# FlexWatch.net
KiCad netlist of a schematic drawn in EAGLE
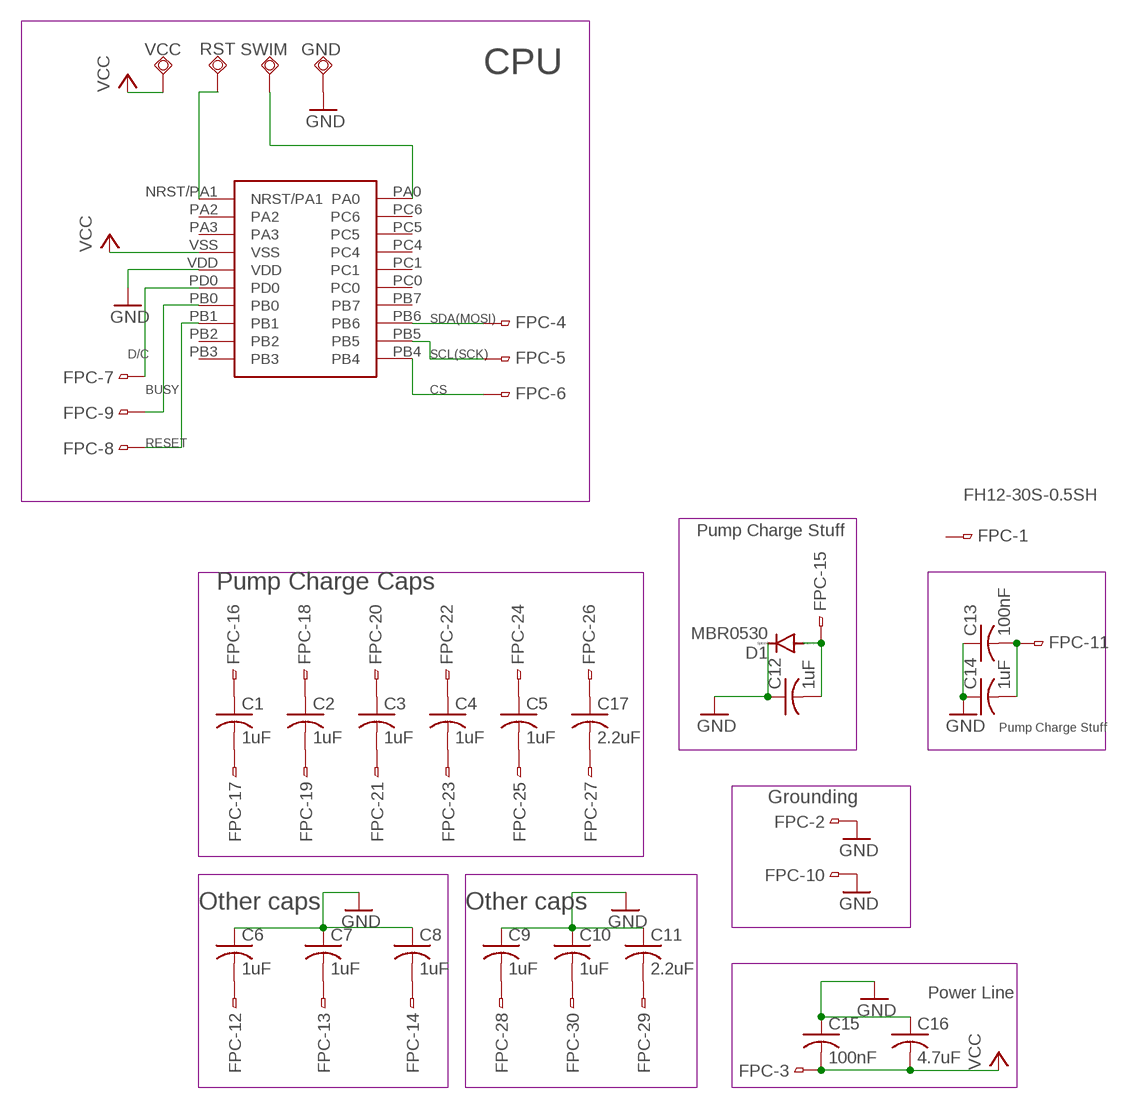
[diagram p0: schematic, sheet 1]

(export (version "E")
  (design (tool "Eeschema 10.0.6"))
  (components
    (comp (ref "C1")
      (value "1uF")
      (footprint "eagle-import:C0805")
      (libsource (lib "eagle-import") (part "C-USC0805"))
    )
    (comp (ref "C2")
      (value "1uF")
      (footprint "eagle-import:C0805")
      (libsource (lib "eagle-import") (part "C-USC0805"))
    )
    (comp (ref "C3")
      (value "1uF")
      (footprint "eagle-import:C0805")
      (libsource (lib "eagle-import") (part "C-USC0805"))
    )
    (comp (ref "C4")
      (value "1uF")
      (footprint "eagle-import:C0805")
      (libsource (lib "eagle-import") (part "C-USC0805"))
    )
    (comp (ref "C5")
      (value "1uF")
      (footprint "eagle-import:C0805")
      (libsource (lib "eagle-import") (part "C-USC0805"))
    )
    (comp (ref "C6")
      (value "1uF")
      (footprint "eagle-import:C0805")
      (libsource (lib "eagle-import") (part "C-USC0805"))
    )
    (comp (ref "C7")
      (value "1uF")
      (footprint "eagle-import:C0805")
      (libsource (lib "eagle-import") (part "C-USC0805"))
    )
    (comp (ref "C8")
      (value "1uF")
      (footprint "eagle-import:C0805")
      (libsource (lib "eagle-import") (part "C-USC0805"))
    )
    (comp (ref "C9")
      (value "1uF")
      (footprint "eagle-import:C0805")
      (libsource (lib "eagle-import") (part "C-USC0805"))
    )
    (comp (ref "C10")
      (value "1uF")
      (footprint "eagle-import:C0805")
      (libsource (lib "eagle-import") (part "C-USC0805"))
    )
    (comp (ref "C11")
      (value "2.2uF")
      (footprint "eagle-import:C1206")
      (libsource (lib "eagle-import") (part "C-USC1206"))
    )
    (comp (ref "C12")
      (value "1uF")
      (footprint "eagle-import:C0805")
      (libsource (lib "eagle-import") (part "C-USC0805"))
    )
    (comp (ref "C13")
      (value "100nF")
      (footprint "eagle-import:C0805")
      (libsource (lib "eagle-import") (part "C-USC0805"))
    )
    (comp (ref "C14")
      (value "1uF")
      (footprint "eagle-import:C0805")
      (libsource (lib "eagle-import") (part "C-USC0805"))
    )
    (comp (ref "C15")
      (value "100nF")
      (footprint "eagle-import:C0805")
      (libsource (lib "eagle-import") (part "C-USC0805"))
    )
    (comp (ref "C16")
      (value "4.7uF")
      (footprint "eagle-import:C0805")
      (libsource (lib "eagle-import") (part "C-USC0805"))
    )
    (comp (ref "C17")
      (value "2.2uF")
      (footprint "eagle-import:C1206")
      (libsource (lib "eagle-import") (part "C-USC1206"))
    )
    (comp (ref "D1")
      (value "MBR0530")
      (footprint "eagle-import:SOD-123_MINI-SMA")
      (libsource (lib "eagle-import") (part "CGRM400-G1"))
    )
    (comp (ref "FPC")
      (value "FH12-30S-0.5SH")
      (footprint "eagle-import:FH12-30S-0.5SH")
      (fields (field (name "MPN") "FH12-30S-0.5SH(55)"))
      (libsource (lib "eagle-import") (part "FH12-30S-0.5SH"))
    )
    (comp (ref "GND")
      (value "TPSQTP18SQ")
      (footprint "eagle-import:TP18SQ")
      (libsource (lib "eagle-import") (part "TPSQTP18SQ"))
    )
    (comp (ref "RST")
      (value "TPSQTP18SQ")
      (footprint "eagle-import:TP18SQ")
      (libsource (lib "eagle-import") (part "TPSQTP18SQ"))
    )
    (comp (ref "SWIM")
      (value "TPSQTP18SQ")
      (footprint "eagle-import:TP18SQ")
      (libsource (lib "eagle-import") (part "TPSQTP18SQ"))
    )
    (comp (ref "U$1")
      (value "STM8L151F3")
      (footprint "eagle-import:UFQFPN-20")
      (libsource (lib "eagle-import") (part "STM8L151F3"))
    )
    (comp (ref "VCC")
      (value "TPSQTP18SQ")
      (footprint "eagle-import:TP18SQ")
      (libsource (lib "eagle-import") (part "TPSQTP18SQ"))
    )
  )
  (nets
    (net (code "1") (name "/BUSY") (class "Default")
      (node (ref "FPC") (pin "9") (pinfunction "1_9") (pintype "passive"))
      (node (ref "U$1") (pin "PB0") (pinfunction "PB0_PB0") (pintype "bidirectional"))
    )
    (net (code "2") (name "/CS") (class "Default")
      (node (ref "FPC") (pin "6") (pinfunction "1_6") (pintype "passive"))
      (node (ref "U$1") (pin "PB4") (pinfunction "PB4_PB4") (pintype "bidirectional"))
    )
    (net (code "3") (name "/D{slash}C") (class "Default")
      (node (ref "FPC") (pin "7") (pinfunction "1_7") (pintype "passive"))
      (node (ref "U$1") (pin "PD0") (pinfunction "PD0_PD0") (pintype "bidirectional"))
    )
    (net (code "4") (name "/RESET") (class "Default")
      (node (ref "FPC") (pin "8") (pinfunction "1_8") (pintype "passive"))
      (node (ref "U$1") (pin "PB1") (pinfunction "PB1_PB1") (pintype "bidirectional"))
    )
    (net (code "5") (name "/SCL(SCK)") (class "Default")
      (node (ref "FPC") (pin "5") (pinfunction "1_5") (pintype "passive"))
      (node (ref "U$1") (pin "PB5") (pinfunction "PB5_PB5") (pintype "bidirectional"))
    )
    (net (code "6") (name "/SDA(MOSI)") (class "Default")
      (node (ref "FPC") (pin "4") (pinfunction "1_4") (pintype "passive"))
      (node (ref "U$1") (pin "PB6") (pinfunction "PB6_PB6") (pintype "bidirectional"))
    )
    (net (code "7") (name "GND") (class "Default")
      (node (ref "C10") (pin "1") (pinfunction "1_1") (pintype "passive"))
      (node (ref "C11") (pin "1") (pinfunction "1_1") (pintype "passive"))
      (node (ref "C12") (pin "1") (pinfunction "1_1") (pintype "passive"))
      (node (ref "C13") (pin "1") (pinfunction "1_1") (pintype "passive"))
      (node (ref "C14") (pin "1") (pinfunction "1_1") (pintype "passive"))
      (node (ref "C15") (pin "1") (pinfunction "1_1") (pintype "passive"))
      (node (ref "C16") (pin "1") (pinfunction "1_1") (pintype "passive"))
      (node (ref "C6") (pin "1") (pinfunction "1_1") (pintype "passive"))
      (node (ref "C7") (pin "1") (pinfunction "1_1") (pintype "passive"))
      (node (ref "C8") (pin "1") (pinfunction "1_1") (pintype "passive"))
      (node (ref "C9") (pin "1") (pinfunction "1_1") (pintype "passive"))
      (node (ref "D1") (pin "C") (pinfunction "C_C") (pintype "passive"))
      (node (ref "FPC") (pin "10") (pinfunction "1_10") (pintype "passive"))
      (node (ref "FPC") (pin "2") (pinfunction "1_2") (pintype "passive"))
      (node (ref "GND") (pin "TP") (pinfunction "TP_TP") (pintype "input"))
      (node (ref "U$1") (pin "VDD") (pinfunction "VDD_VDD") (pintype "bidirectional"))
    )
    (net (code "8") (name "Net-(FPCC-1)") (class "Default")
      (node (ref "C13") (pin "2") (pinfunction "2_2") (pintype "passive"))
      (node (ref "C14") (pin "2") (pinfunction "2_2") (pintype "passive"))
      (node (ref "FPC") (pin "11") (pinfunction "1_11") (pintype "passive"))
    )
    (net (code "9") (name "Net-(FPCD-1)") (class "Default")
      (node (ref "C6") (pin "2") (pinfunction "2_2") (pintype "passive"))
      (node (ref "FPC") (pin "12") (pinfunction "1_12") (pintype "passive"))
    )
    (net (code "10") (name "Net-(FPCE-1)") (class "Default")
      (node (ref "C7") (pin "2") (pinfunction "2_2") (pintype "passive"))
      (node (ref "FPC") (pin "13") (pinfunction "1_13") (pintype "passive"))
    )
    (net (code "11") (name "Net-(FPCF-1)") (class "Default")
      (node (ref "C8") (pin "2") (pinfunction "2_2") (pintype "passive"))
      (node (ref "FPC") (pin "14") (pinfunction "1_14") (pintype "passive"))
    )
    (net (code "12") (name "Net-(FPCG-1)") (class "Default")
      (node (ref "C12") (pin "2") (pinfunction "2_2") (pintype "passive"))
      (node (ref "D1") (pin "A") (pinfunction "A_A") (pintype "passive"))
      (node (ref "FPC") (pin "15") (pinfunction "1_15") (pintype "passive"))
    )
    (net (code "13") (name "Net-(FPCH-1)") (class "Default")
      (node (ref "C1") (pin "1") (pinfunction "1_1") (pintype "passive"))
      (node (ref "FPC") (pin "16") (pinfunction "1_16") (pintype "passive"))
    )
    (net (code "14") (name "Net-(FPCI-1)") (class "Default")
      (node (ref "C1") (pin "2") (pinfunction "2_2") (pintype "passive"))
      (node (ref "FPC") (pin "17") (pinfunction "1_17") (pintype "passive"))
    )
    (net (code "15") (name "Net-(FPCJ-1)") (class "Default")
      (node (ref "C2") (pin "1") (pinfunction "1_1") (pintype "passive"))
      (node (ref "FPC") (pin "18") (pinfunction "1_18") (pintype "passive"))
    )
    (net (code "16") (name "Net-(FPCK-1)") (class "Default")
      (node (ref "C2") (pin "2") (pinfunction "2_2") (pintype "passive"))
      (node (ref "FPC") (pin "19") (pinfunction "1_19") (pintype "passive"))
    )
    (net (code "17") (name "Net-(FPCM-1)") (class "Default")
      (node (ref "C3") (pin "1") (pinfunction "1_1") (pintype "passive"))
      (node (ref "FPC") (pin "20") (pinfunction "1_20") (pintype "passive"))
    )
    (net (code "18") (name "Net-(FPCN-1)") (class "Default")
      (node (ref "C3") (pin "2") (pinfunction "2_2") (pintype "passive"))
      (node (ref "FPC") (pin "21") (pinfunction "1_21") (pintype "passive"))
    )
    (net (code "19") (name "Net-(FPCO-1)") (class "Default")
      (node (ref "C4") (pin "1") (pinfunction "1_1") (pintype "passive"))
      (node (ref "FPC") (pin "22") (pinfunction "1_22") (pintype "passive"))
    )
    (net (code "20") (name "Net-(FPCP-1)") (class "Default")
      (node (ref "C4") (pin "2") (pinfunction "2_2") (pintype "passive"))
      (node (ref "FPC") (pin "23") (pinfunction "1_23") (pintype "passive"))
    )
    (net (code "21") (name "Net-(FPCQ-1)") (class "Default")
      (node (ref "C5") (pin "1") (pinfunction "1_1") (pintype "passive"))
      (node (ref "FPC") (pin "24") (pinfunction "1_24") (pintype "passive"))
    )
    (net (code "22") (name "Net-(FPCR-1)") (class "Default")
      (node (ref "C5") (pin "2") (pinfunction "2_2") (pintype "passive"))
      (node (ref "FPC") (pin "25") (pinfunction "1_25") (pintype "passive"))
    )
    (net (code "23") (name "Net-(FPCS-1)") (class "Default")
      (node (ref "C17") (pin "1") (pinfunction "1_1") (pintype "passive"))
      (node (ref "FPC") (pin "26") (pinfunction "1_26") (pintype "passive"))
    )
    (net (code "24") (name "Net-(FPCT-1)") (class "Default")
      (node (ref "C17") (pin "2") (pinfunction "2_2") (pintype "passive"))
      (node (ref "FPC") (pin "27") (pinfunction "1_27") (pintype "passive"))
    )
    (net (code "25") (name "Net-(FPCU-1)") (class "Default")
      (node (ref "C9") (pin "2") (pinfunction "2_2") (pintype "passive"))
      (node (ref "FPC") (pin "28") (pinfunction "1_28") (pintype "passive"))
    )
    (net (code "26") (name "Net-(FPCV-1)") (class "Default")
      (node (ref "C11") (pin "2") (pinfunction "2_2") (pintype "passive"))
      (node (ref "FPC") (pin "29") (pinfunction "1_29") (pintype "passive"))
    )
    (net (code "27") (name "Net-(FPCX-1)") (class "Default")
      (node (ref "C10") (pin "2") (pinfunction "2_2") (pintype "passive"))
      (node (ref "FPC") (pin "30") (pinfunction "1_30") (pintype "passive"))
    )
    (net (code "28") (name "Net-(RST-PadTP)") (class "Default")
      (node (ref "RST") (pin "TP") (pinfunction "TP_TP") (pintype "input"))
      (node (ref "U$1") (pin "NRST/PA1") (pinfunction "NRST/PA1_NRST/PA1") (pintype "bidirectional"))
    )
    (net (code "29") (name "Net-(SWIM-PadTP)") (class "Default")
      (node (ref "SWIM") (pin "TP") (pinfunction "TP_TP") (pintype "input"))
      (node (ref "U$1") (pin "PA0") (pinfunction "PA0_PA0") (pintype "bidirectional"))
    )
    (net (code "30") (name "VCC") (class "Default")
      (node (ref "C15") (pin "2") (pinfunction "2_2") (pintype "passive"))
      (node (ref "C16") (pin "2") (pinfunction "2_2") (pintype "passive"))
      (node (ref "FPC") (pin "3") (pinfunction "1_3") (pintype "passive"))
      (node (ref "U$1") (pin "VSS") (pinfunction "VSS_VSS") (pintype "bidirectional"))
      (node (ref "VCC") (pin "TP") (pinfunction "TP_TP") (pintype "input"))
    )
    (net (code "31") (name "unconnected-(FPC-Pad1)") (class "Default")
      (node (ref "FPC") (pin "1") (pinfunction "1_1") (pintype "passive"))
    )
    (net (code "32") (name "unconnected-(U$1-PadPA2)") (class "Default")
      (node (ref "U$1") (pin "PA2") (pinfunction "PA2_PA2") (pintype "bidirectional"))
    )
    (net (code "33") (name "unconnected-(U$1-PadPA3)") (class "Default")
      (node (ref "U$1") (pin "PA3") (pinfunction "PA3_PA3") (pintype "bidirectional"))
    )
    (net (code "34") (name "unconnected-(U$1-PadPB2)") (class "Default")
      (node (ref "U$1") (pin "PB2") (pinfunction "PB2_PB2") (pintype "bidirectional"))
    )
    (net (code "35") (name "unconnected-(U$1-PadPB3)") (class "Default")
      (node (ref "U$1") (pin "PB3") (pinfunction "PB3_PB3") (pintype "bidirectional"))
    )
    (net (code "36") (name "unconnected-(U$1-PadPB7)") (class "Default")
      (node (ref "U$1") (pin "PB7") (pinfunction "PB7_PB7") (pintype "bidirectional"))
    )
    (net (code "37") (name "unconnected-(U$1-PadPC0)") (class "Default")
      (node (ref "U$1") (pin "PC0") (pinfunction "PC0_PC0") (pintype "bidirectional"))
    )
    (net (code "38") (name "unconnected-(U$1-PadPC1)") (class "Default")
      (node (ref "U$1") (pin "PC1") (pinfunction "PC1_PC1") (pintype "bidirectional"))
    )
    (net (code "39") (name "unconnected-(U$1-PadPC4)") (class "Default")
      (node (ref "U$1") (pin "PC4") (pinfunction "PC4_PC4") (pintype "bidirectional"))
    )
    (net (code "40") (name "unconnected-(U$1-PadPC5)") (class "Default")
      (node (ref "U$1") (pin "PC5") (pinfunction "PC5_PC5") (pintype "bidirectional"))
    )
    (net (code "41") (name "unconnected-(U$1-PadPC6)") (class "Default")
      (node (ref "U$1") (pin "PC6") (pinfunction "PC6_PC6") (pintype "bidirectional"))
    )
  )
)
